# ALU_AND.net
KiCad netlist of a schematic drawn in Altium Designer
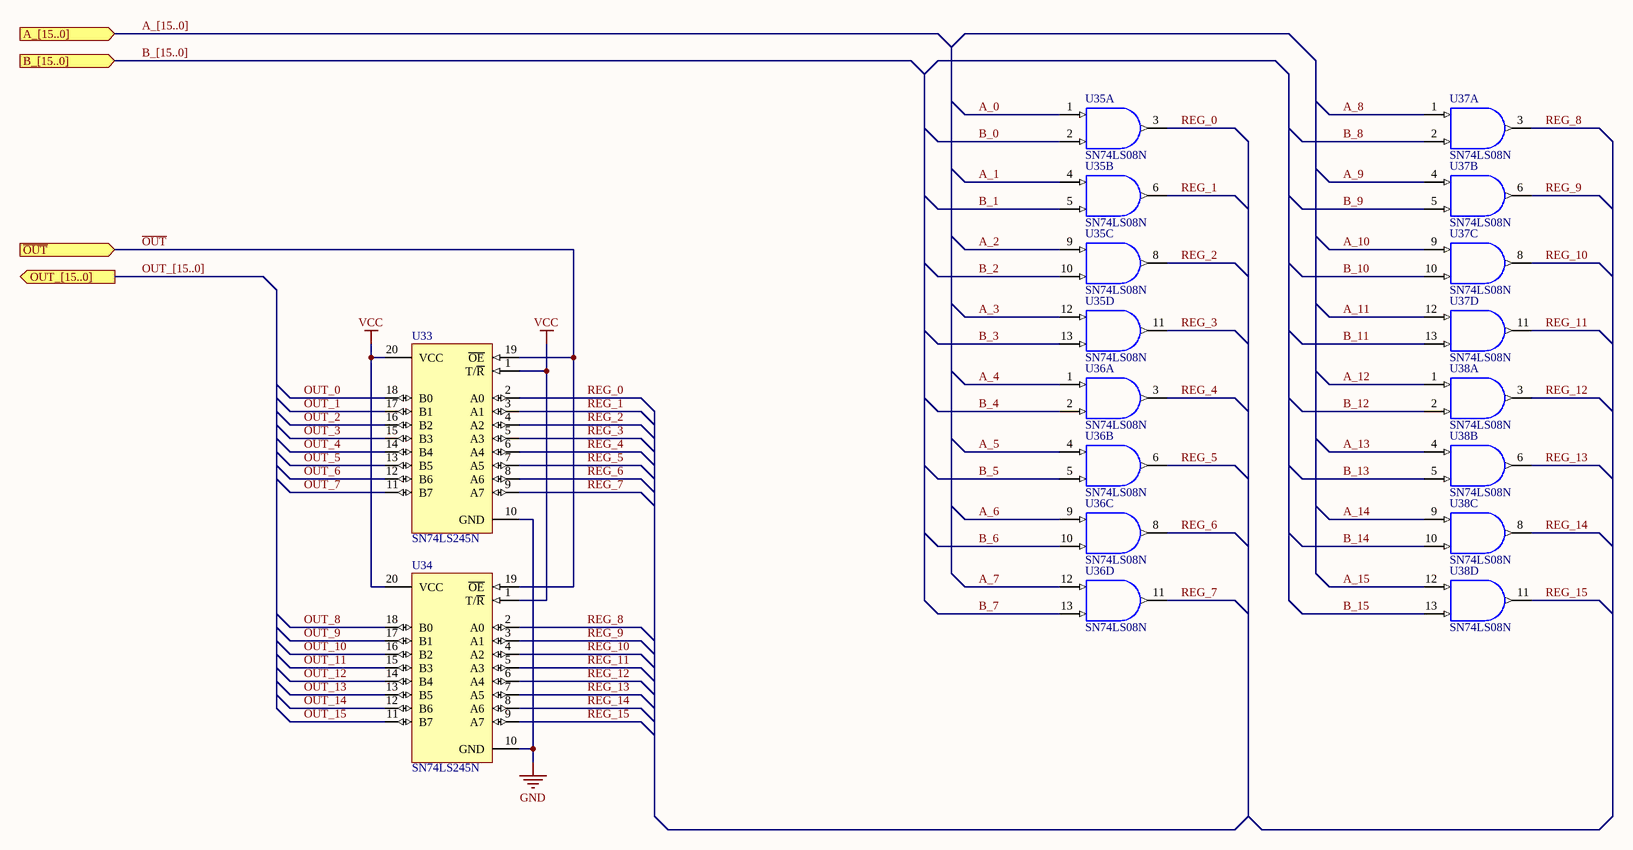
[diagram p0: ALU_AND.SchDoc]

(export (version "E")
  (design (tool "Eeschema 10.0.6"))
  (components
    (comp (ref "U33")
      (value "SN74LS245N")
      (footprint "N020")
      (description "Octal Bus Transceiver with 3-State Outputs")
      (fields (field (name "PUBLISHER") "Altium Limited"))
      (libsource (lib "TI Interface 8-Bit Line Transceiver") (part "SN74LS245N"))
    )
    (comp (ref "U34")
      (value "SN74LS245N")
      (footprint "N020")
      (description "Octal Bus Transceiver with 3-State Outputs")
      (fields (field (name "PUBLISHER") "Altium Limited"))
      (libsource (lib "TI Interface 8-Bit Line Transceiver") (part "SN74LS245N"))
    )
    (comp (ref "U35")
      (value "SN74LS08N")
      (footprint "N014")
      (description "Quadruple 2-Input Positive-AND Gate")
      (fields (field (name "PUBLISHER") "Altium Limited"))
      (libsource (lib "TI Logic Gate 2") (part "SN74LS08N"))
    )
    (comp (ref "U36")
      (value "SN74LS08N")
      (footprint "N014")
      (description "Quadruple 2-Input Positive-AND Gate")
      (fields (field (name "PUBLISHER") "Altium Limited"))
      (libsource (lib "TI Logic Gate 2") (part "SN74LS08N"))
    )
    (comp (ref "U37")
      (value "SN74LS08N")
      (footprint "N014")
      (description "Quadruple 2-Input Positive-AND Gate")
      (fields (field (name "PUBLISHER") "Altium Limited"))
      (libsource (lib "TI Logic Gate 2") (part "SN74LS08N"))
    )
    (comp (ref "U38")
      (value "SN74LS08N")
      (footprint "N014")
      (description "Quadruple 2-Input Positive-AND Gate")
      (fields (field (name "PUBLISHER") "Altium Limited"))
      (libsource (lib "TI Logic Gate 2") (part "SN74LS08N"))
    )
  )
  (nets
    (net (code "1") (name "/A_0") (class "Default")
      (node (ref "U35") (pin "1") (pinfunction "A_1") (pintype "input"))
    )
    (net (code "2") (name "/A_1") (class "Default")
      (node (ref "U35") (pin "4") (pinfunction "A_4") (pintype "input"))
    )
    (net (code "3") (name "/A_2") (class "Default")
      (node (ref "U35") (pin "9") (pinfunction "A_9") (pintype "input"))
    )
    (net (code "4") (name "/A_3") (class "Default")
      (node (ref "U35") (pin "12") (pinfunction "A_12") (pintype "input"))
    )
    (net (code "5") (name "/A_4") (class "Default")
      (node (ref "U36") (pin "1") (pinfunction "A_1") (pintype "input"))
    )
    (net (code "6") (name "/A_5") (class "Default")
      (node (ref "U36") (pin "4") (pinfunction "A_4") (pintype "input"))
    )
    (net (code "7") (name "/A_6") (class "Default")
      (node (ref "U36") (pin "9") (pinfunction "A_9") (pintype "input"))
    )
    (net (code "8") (name "/A_7") (class "Default")
      (node (ref "U36") (pin "12") (pinfunction "A_12") (pintype "input"))
    )
    (net (code "9") (name "/A_8") (class "Default")
      (node (ref "U37") (pin "1") (pinfunction "A_1") (pintype "input"))
    )
    (net (code "10") (name "/A_9") (class "Default")
      (node (ref "U37") (pin "4") (pinfunction "A_4") (pintype "input"))
    )
    (net (code "11") (name "/A_10") (class "Default")
      (node (ref "U37") (pin "9") (pinfunction "A_9") (pintype "input"))
    )
    (net (code "12") (name "/A_11") (class "Default")
      (node (ref "U37") (pin "12") (pinfunction "A_12") (pintype "input"))
    )
    (net (code "13") (name "/A_12") (class "Default")
      (node (ref "U38") (pin "1") (pinfunction "A_1") (pintype "input"))
    )
    (net (code "14") (name "/A_13") (class "Default")
      (node (ref "U38") (pin "4") (pinfunction "A_4") (pintype "input"))
    )
    (net (code "15") (name "/A_14") (class "Default")
      (node (ref "U38") (pin "9") (pinfunction "A_9") (pintype "input"))
    )
    (net (code "16") (name "/A_15") (class "Default")
      (node (ref "U38") (pin "12") (pinfunction "A_12") (pintype "input"))
    )
    (net (code "18") (name "/B_0") (class "Default")
      (node (ref "U35") (pin "2") (pinfunction "B_2") (pintype "input"))
    )
    (net (code "19") (name "/B_1") (class "Default")
      (node (ref "U35") (pin "5") (pinfunction "B_5") (pintype "input"))
    )
    (net (code "20") (name "/B_2") (class "Default")
      (node (ref "U35") (pin "10") (pinfunction "B_10") (pintype "input"))
    )
    (net (code "21") (name "/B_3") (class "Default")
      (node (ref "U35") (pin "13") (pinfunction "B_13") (pintype "input"))
    )
    (net (code "22") (name "/B_4") (class "Default")
      (node (ref "U36") (pin "2") (pinfunction "B_2") (pintype "input"))
    )
    (net (code "23") (name "/B_5") (class "Default")
      (node (ref "U36") (pin "5") (pinfunction "B_5") (pintype "input"))
    )
    (net (code "24") (name "/B_6") (class "Default")
      (node (ref "U36") (pin "10") (pinfunction "B_10") (pintype "input"))
    )
    (net (code "25") (name "/B_7") (class "Default")
      (node (ref "U36") (pin "13") (pinfunction "B_13") (pintype "input"))
    )
    (net (code "26") (name "/B_8") (class "Default")
      (node (ref "U37") (pin "2") (pinfunction "B_2") (pintype "input"))
    )
    (net (code "27") (name "/B_9") (class "Default")
      (node (ref "U37") (pin "5") (pinfunction "B_5") (pintype "input"))
    )
    (net (code "28") (name "/B_10") (class "Default")
      (node (ref "U37") (pin "10") (pinfunction "B_10") (pintype "input"))
    )
    (net (code "29") (name "/B_11") (class "Default")
      (node (ref "U37") (pin "13") (pinfunction "B_13") (pintype "input"))
    )
    (net (code "30") (name "/B_12") (class "Default")
      (node (ref "U38") (pin "2") (pinfunction "B_2") (pintype "input"))
    )
    (net (code "31") (name "/B_13") (class "Default")
      (node (ref "U38") (pin "5") (pinfunction "B_5") (pintype "input"))
    )
    (net (code "32") (name "/B_14") (class "Default")
      (node (ref "U38") (pin "10") (pinfunction "B_10") (pintype "input"))
    )
    (net (code "33") (name "/B_15") (class "Default")
      (node (ref "U38") (pin "13") (pinfunction "B_13") (pintype "input"))
    )
    (net (code "35") (name "/OUT_0") (class "Default")
      (node (ref "U33") (pin "18") (pinfunction "B0_18") (pintype "bidirectional"))
    )
    (net (code "36") (name "/OUT_1") (class "Default")
      (node (ref "U33") (pin "17") (pinfunction "B1_17") (pintype "bidirectional"))
    )
    (net (code "37") (name "/OUT_2") (class "Default")
      (node (ref "U33") (pin "16") (pinfunction "B2_16") (pintype "bidirectional"))
    )
    (net (code "38") (name "/OUT_3") (class "Default")
      (node (ref "U33") (pin "15") (pinfunction "B3_15") (pintype "bidirectional"))
    )
    (net (code "39") (name "/OUT_4") (class "Default")
      (node (ref "U33") (pin "14") (pinfunction "B4_14") (pintype "bidirectional"))
    )
    (net (code "40") (name "/OUT_5") (class "Default")
      (node (ref "U33") (pin "13") (pinfunction "B5_13") (pintype "bidirectional"))
    )
    (net (code "41") (name "/OUT_6") (class "Default")
      (node (ref "U33") (pin "12") (pinfunction "B6_12") (pintype "bidirectional"))
    )
    (net (code "42") (name "/OUT_7") (class "Default")
      (node (ref "U33") (pin "11") (pinfunction "B7_11") (pintype "bidirectional"))
    )
    (net (code "43") (name "/OUT_8") (class "Default")
      (node (ref "U34") (pin "18") (pinfunction "B0_18") (pintype "bidirectional"))
    )
    (net (code "44") (name "/OUT_9") (class "Default")
      (node (ref "U34") (pin "17") (pinfunction "B1_17") (pintype "bidirectional"))
    )
    (net (code "45") (name "/OUT_10") (class "Default")
      (node (ref "U34") (pin "16") (pinfunction "B2_16") (pintype "bidirectional"))
    )
    (net (code "46") (name "/OUT_11") (class "Default")
      (node (ref "U34") (pin "15") (pinfunction "B3_15") (pintype "bidirectional"))
    )
    (net (code "47") (name "/OUT_12") (class "Default")
      (node (ref "U34") (pin "14") (pinfunction "B4_14") (pintype "bidirectional"))
    )
    (net (code "48") (name "/OUT_13") (class "Default")
      (node (ref "U34") (pin "13") (pinfunction "B5_13") (pintype "bidirectional"))
    )
    (net (code "49") (name "/OUT_14") (class "Default")
      (node (ref "U34") (pin "12") (pinfunction "B6_12") (pintype "bidirectional"))
    )
    (net (code "50") (name "/OUT_15") (class "Default")
      (node (ref "U34") (pin "11") (pinfunction "B7_11") (pintype "bidirectional"))
    )
    (net (code "52") (name "/REG_0") (class "Default")
      (node (ref "U33") (pin "2") (pinfunction "A0_2") (pintype "bidirectional"))
      (node (ref "U35") (pin "3") (pinfunction "Y_3") (pintype "output"))
    )
    (net (code "53") (name "/REG_1") (class "Default")
      (node (ref "U33") (pin "3") (pinfunction "A1_3") (pintype "bidirectional"))
      (node (ref "U35") (pin "6") (pinfunction "Y_6") (pintype "output"))
    )
    (net (code "54") (name "/REG_2") (class "Default")
      (node (ref "U33") (pin "4") (pinfunction "A2_4") (pintype "bidirectional"))
      (node (ref "U35") (pin "8") (pinfunction "Y_8") (pintype "output"))
    )
    (net (code "55") (name "/REG_3") (class "Default")
      (node (ref "U33") (pin "5") (pinfunction "A3_5") (pintype "bidirectional"))
      (node (ref "U35") (pin "11") (pinfunction "Y_11") (pintype "output"))
    )
    (net (code "56") (name "/REG_4") (class "Default")
      (node (ref "U33") (pin "6") (pinfunction "A4_6") (pintype "bidirectional"))
      (node (ref "U36") (pin "3") (pinfunction "Y_3") (pintype "output"))
    )
    (net (code "57") (name "/REG_5") (class "Default")
      (node (ref "U33") (pin "7") (pinfunction "A5_7") (pintype "bidirectional"))
      (node (ref "U36") (pin "6") (pinfunction "Y_6") (pintype "output"))
    )
    (net (code "58") (name "/REG_6") (class "Default")
      (node (ref "U33") (pin "8") (pinfunction "A6_8") (pintype "bidirectional"))
      (node (ref "U36") (pin "8") (pinfunction "Y_8") (pintype "output"))
    )
    (net (code "59") (name "/REG_7") (class "Default")
      (node (ref "U33") (pin "9") (pinfunction "A7_9") (pintype "bidirectional"))
      (node (ref "U36") (pin "11") (pinfunction "Y_11") (pintype "output"))
    )
    (net (code "60") (name "/REG_8") (class "Default")
      (node (ref "U34") (pin "2") (pinfunction "A0_2") (pintype "bidirectional"))
      (node (ref "U37") (pin "3") (pinfunction "Y_3") (pintype "output"))
    )
    (net (code "61") (name "/REG_9") (class "Default")
      (node (ref "U34") (pin "3") (pinfunction "A1_3") (pintype "bidirectional"))
      (node (ref "U37") (pin "6") (pinfunction "Y_6") (pintype "output"))
    )
    (net (code "62") (name "/REG_10") (class "Default")
      (node (ref "U34") (pin "4") (pinfunction "A2_4") (pintype "bidirectional"))
      (node (ref "U37") (pin "8") (pinfunction "Y_8") (pintype "output"))
    )
    (net (code "63") (name "/REG_11") (class "Default")
      (node (ref "U34") (pin "5") (pinfunction "A3_5") (pintype "bidirectional"))
      (node (ref "U37") (pin "11") (pinfunction "Y_11") (pintype "output"))
    )
    (net (code "64") (name "/REG_12") (class "Default")
      (node (ref "U34") (pin "6") (pinfunction "A4_6") (pintype "bidirectional"))
      (node (ref "U38") (pin "3") (pinfunction "Y_3") (pintype "output"))
    )
    (net (code "65") (name "/REG_13") (class "Default")
      (node (ref "U34") (pin "7") (pinfunction "A5_7") (pintype "bidirectional"))
      (node (ref "U38") (pin "6") (pinfunction "Y_6") (pintype "output"))
    )
    (net (code "66") (name "/REG_14") (class "Default")
      (node (ref "U34") (pin "8") (pinfunction "A6_8") (pintype "bidirectional"))
      (node (ref "U38") (pin "8") (pinfunction "Y_8") (pintype "output"))
    )
    (net (code "67") (name "/REG_15") (class "Default")
      (node (ref "U34") (pin "9") (pinfunction "A7_9") (pintype "bidirectional"))
      (node (ref "U38") (pin "11") (pinfunction "Y_11") (pintype "output"))
    )
    (net (code "68") (name "/~{OUT}") (class "Default")
      (node (ref "U33") (pin "19") (pinfunction "~{OE}_19") (pintype "input"))
      (node (ref "U34") (pin "19") (pinfunction "~{OE}_19") (pintype "input"))
    )
    (net (code "69") (name "GND") (class "Default")
      (node (ref "U33") (pin "10") (pinfunction "GND_10") (pintype "power_in"))
      (node (ref "U34") (pin "10") (pinfunction "GND_10") (pintype "power_in"))
      (node (ref "U35") (pin "7") (pinfunction "GND_7") (pintype "power_in"))
      (node (ref "U36") (pin "7") (pinfunction "GND_7") (pintype "power_in"))
      (node (ref "U37") (pin "7") (pinfunction "GND_7") (pintype "power_in"))
      (node (ref "U38") (pin "7") (pinfunction "GND_7") (pintype "power_in"))
    )
    (net (code "70") (name "VCC") (class "Default")
      (node (ref "U33") (pin "1") (pinfunction "T/~{R}_1") (pintype "input"))
      (node (ref "U33") (pin "20") (pinfunction "VCC_20") (pintype "power_in"))
      (node (ref "U34") (pin "1") (pinfunction "T/~{R}_1") (pintype "input"))
      (node (ref "U34") (pin "20") (pinfunction "VCC_20") (pintype "power_in"))
      (node (ref "U35") (pin "14") (pinfunction "VCC_14") (pintype "power_in"))
      (node (ref "U36") (pin "14") (pinfunction "VCC_14") (pintype "power_in"))
      (node (ref "U37") (pin "14") (pinfunction "VCC_14") (pintype "power_in"))
      (node (ref "U38") (pin "14") (pinfunction "VCC_14") (pintype "power_in"))
    )
  )
)
